# E.net
KiCad netlist of a schematic drawn in Altium Designer
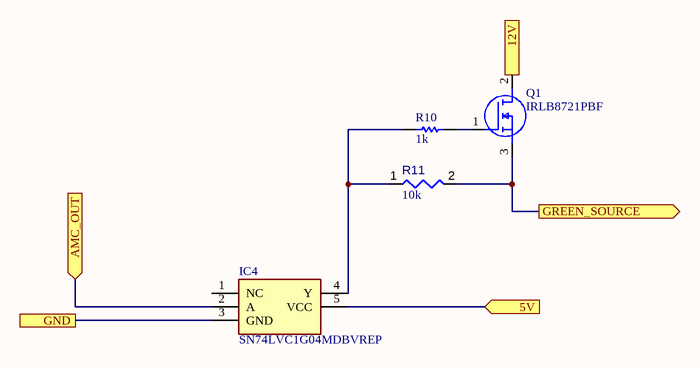
[diagram p0: E.SchDoc]

(export (version "E")
  (design (tool "Eeschema 10.0.6"))
  (components
    (comp (ref "IC4")
      (value "SN74LVC1G04MDBVREP")
      (footprint "SamacSys:SOT95P280X145-5N")
      (description "Integrated Circuit")
      (fields (field (name "MOUSER PART NUMBER") "595-SN74LVC04MDBVREP"))
      (libsource (lib "*") (part "SN74LVC1G04MDBVREP"))
    )
    (comp (ref "Q1")
      (value "IRLB8721PBF")
      (footprint "SamacSys:TO254P483X1016X1994-3P")
      (description "MOSFET (N-Channel)")
      (fields (field (name "MOUSER PART NUMBER") "942-IRLB8721PBF"))
      (libsource (lib "*") (part "IRLB8721PBF"))
    )
    (comp (ref "R10")
      (value "1k")
      (footprint "RESC3116X70X50ML13T20")
      (description "Chip Resistor, 1 KOhm, +/- 1%, 0.25 W, -55 to 155 degC, 1206 (3216 Metric)")
      (fields (field (name "TOLERANCE") "1%") (field (name "POWER") "250mW"))
      (libsource (lib "") (part "RES-2_1"))
    )
    (comp (ref "R11")
      (value "10k")
      (footprint "RESC2013X50X35ML15T15")
      (description "Chip Resistor, 10 KOhm, +/- 1%, 125 mW, -55 to 155 degC, 0805 (2012 Metric)")
      (fields (field (name "TOLERANCE") "1%") (field (name "POWER") "125mW"))
      (libsource (lib "Hector Dela Rosa") (part "RES-2"))
    )
  )
  (nets
    (net (code "1") (name "/5V") (class "Default")
      (node (ref "IC4") (pin "5") (pinfunction "VCC_5") (pintype "passive"))
    )
    (net (code "2") (name "/12V") (class "Default")
      (node (ref "Q1") (pin "2") (pinfunction "D_2") (pintype "passive"))
    )
    (net (code "3") (name "/AMC_OUT") (class "Default")
      (node (ref "IC4") (pin "2") (pinfunction "A_2") (pintype "passive"))
    )
    (net (code "4") (name "/GND") (class "Default")
      (node (ref "IC4") (pin "3") (pinfunction "GND_3") (pintype "passive"))
    )
    (net (code "5") (name "/GREEN_SOURCE") (class "Default")
      (node (ref "Q1") (pin "3") (pinfunction "S_3") (pintype "passive"))
      (node (ref "R11") (pin "2") (pinfunction "2_2") (pintype "passive"))
    )
    (net (code "6") (name "Net-(IC4-Y)") (class "Default")
      (node (ref "IC4") (pin "4") (pinfunction "Y_4") (pintype "passive"))
      (node (ref "R10") (pin "1") (pinfunction "1_1") (pintype "passive"))
      (node (ref "R11") (pin "1") (pinfunction "1_1") (pintype "passive"))
    )
    (net (code "7") (name "Net-(Q1-G)") (class "Default")
      (node (ref "Q1") (pin "1") (pinfunction "G_1") (pintype "passive"))
      (node (ref "R10") (pin "2") (pinfunction "2_2") (pintype "passive"))
    )
    (net (code "8") (name "unconnected-(IC4-NC-Pad1)") (class "Default")
      (node (ref "IC4") (pin "1") (pinfunction "NC_1") (pintype "passive"))
    )
  )
)
